# MAIN.net
KiCad netlist of a schematic drawn in Altium Designer
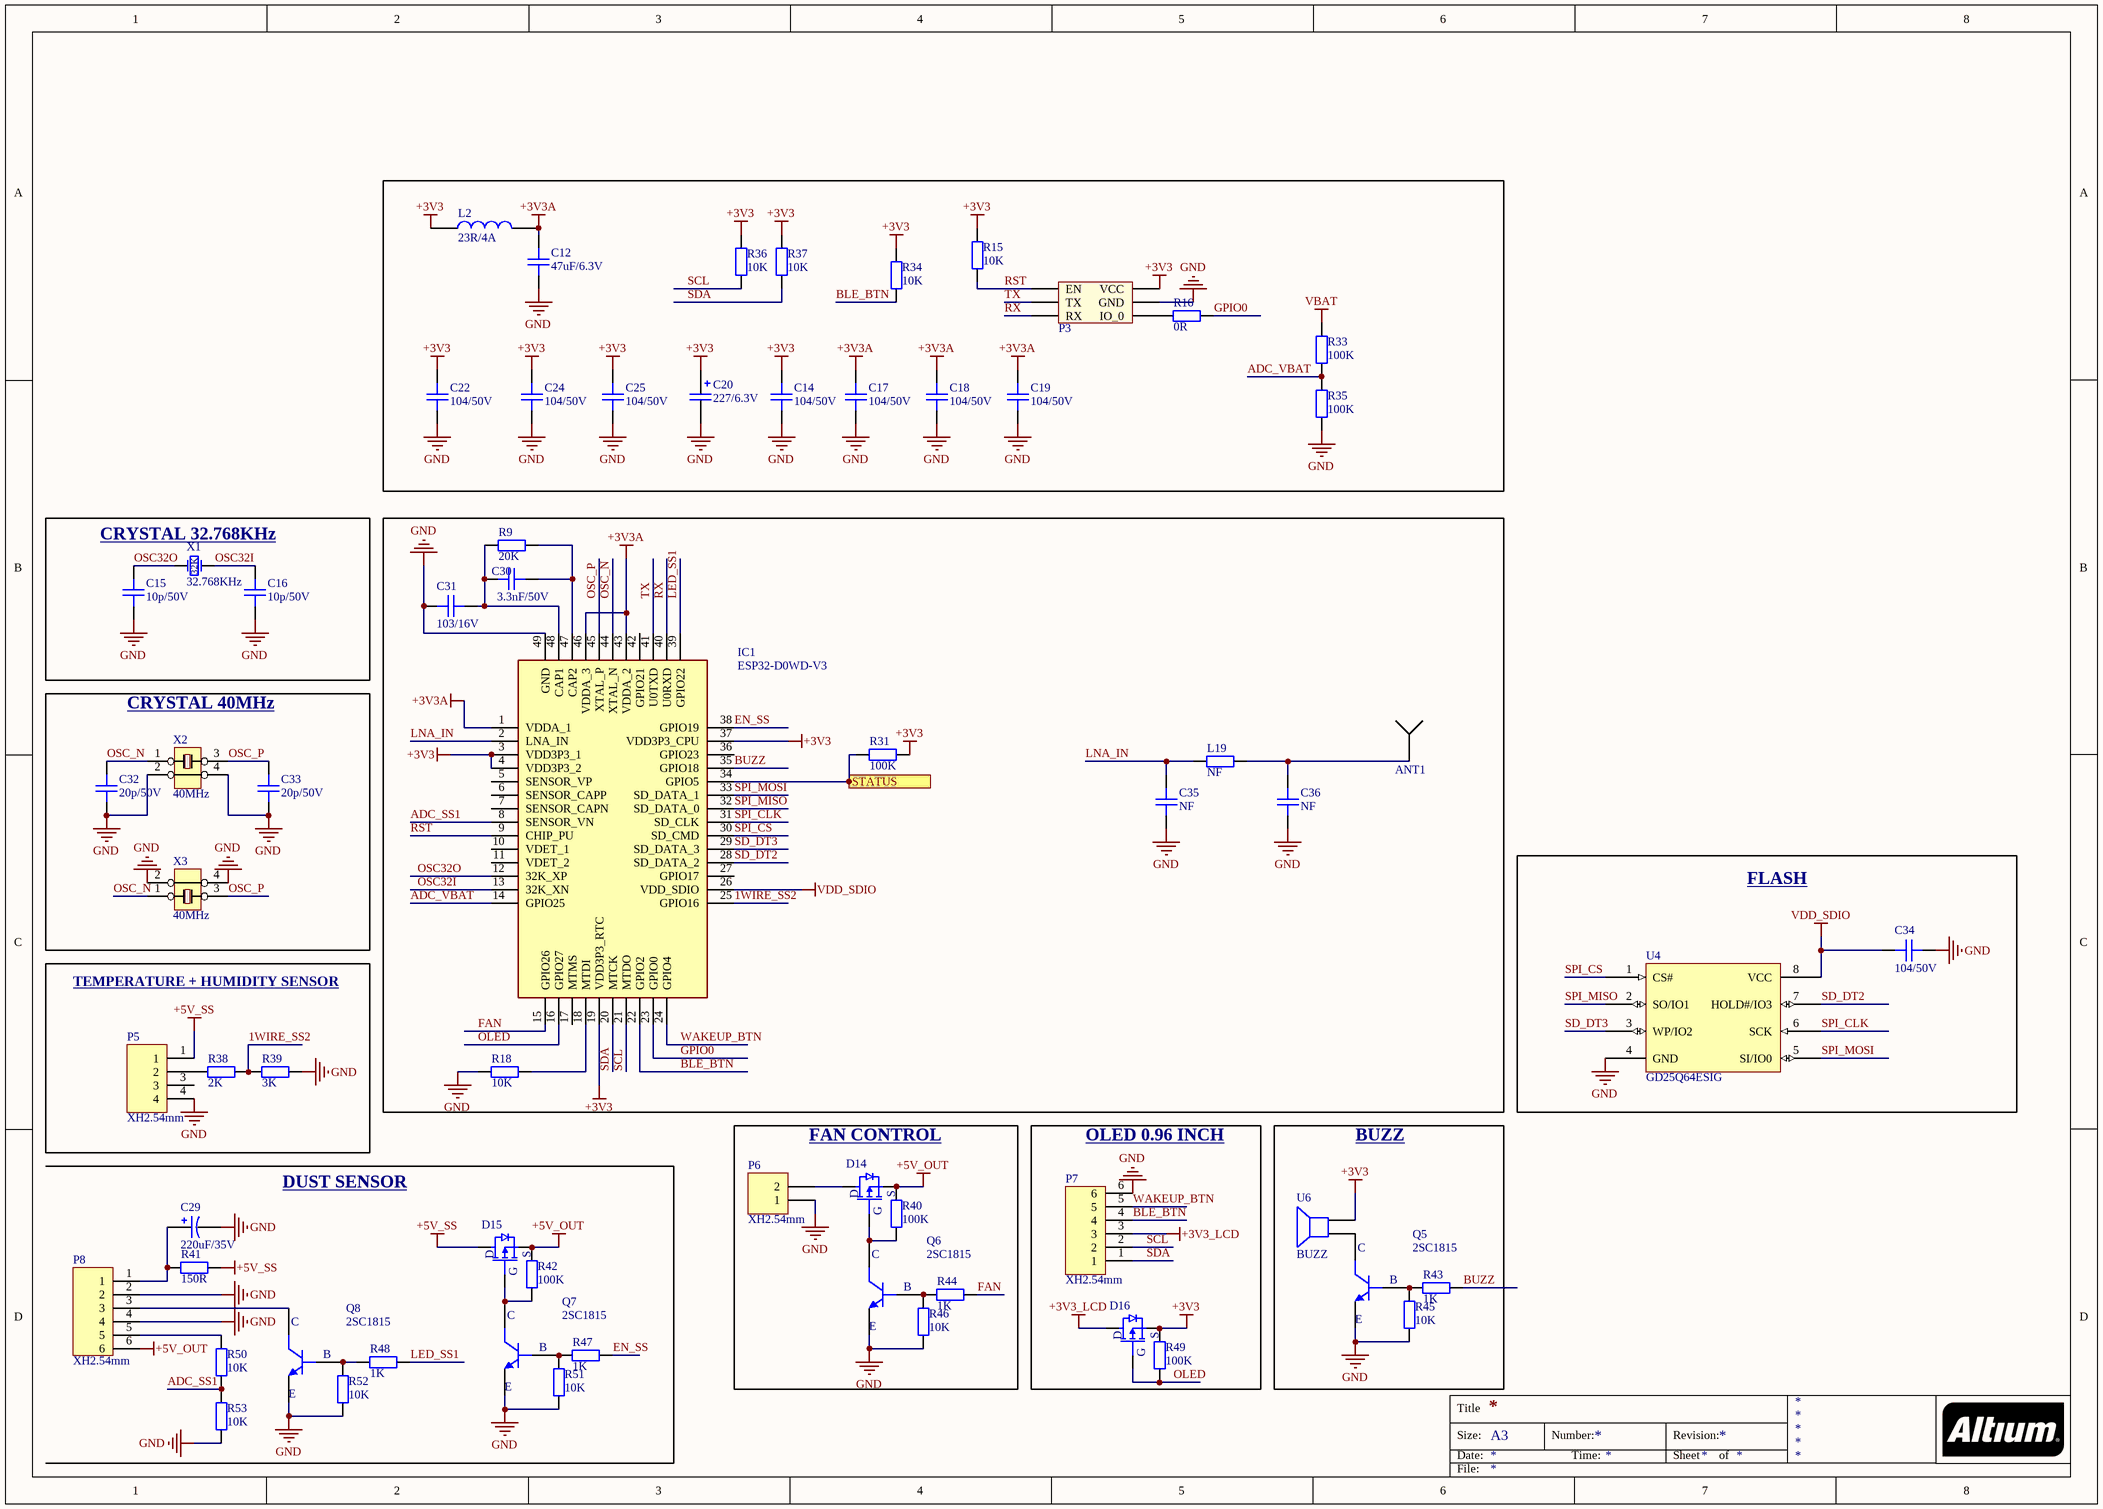
[diagram p0: MAIN.SchDoc]

(export (version "E")
  (design (tool "Eeschema 10.0.6"))
  (components
    (comp (ref "ANT1") (value "~") (footprint "SWRU120D") (libsource (lib "06.PCB Anten") (part "SWRU120D")))
    (comp (ref "C12")
      (value "47uF/6.3V")
      (footprint "CAPC-0603 (1608) - HD")
      (description "CAP CER 47UF 6.3V X5R 0603")
      (fields (field (name "MPN") "GMC10X5R476M6R3NT") (field (name "MFR") "CAL-CHIP ELECTRONICS, INC."))
      (libsource (lib "01.Passives") (part "GMC10X5R476M6R3NT"))
    )
    (comp (ref "C14")
      (value "104/50V")
      (footprint "CAPC-0603 (1608) - HD")
      (description "CAP CER 0.1uF 50V 10% X7R 0603")
      (fields (field (name "MPN") "C0603C104K5RACTU"))
      (libsource (lib "01.Passives") (part "C0603C104K5RACTU"))
    )
    (comp (ref "C15")
      (value "10p/50V")
      (footprint "CAPC-0603 (1608) - HD")
      (description "CAP CER 10pF 5% 50V NP0 0603")
      (fields (field (name "MPN") "CL10C100JB8NNND") (field (name "MFR") "Samsung Electro-Mechanics"))
      (libsource (lib "01.Passives 2") (part "CL10C100JB8NNND"))
    )
    (comp (ref "C16")
      (value "10p/50V")
      (footprint "CAPC-0603 (1608) - HD")
      (description "CAP CER 10pF 5% 50V NP0 0603")
      (fields (field (name "MPN") "CL10C100JB8NNND") (field (name "MFR") "Samsung Electro-Mechanics"))
      (libsource (lib "01.Passives 2") (part "CL10C100JB8NNND"))
    )
    (comp (ref "C17")
      (value "104/50V")
      (footprint "CAPC-0603 (1608) - HD")
      (description "CAP CER 0.1uF 50V 10% X7R 0603")
      (fields (field (name "MPN") "C0603C104K5RACTU"))
      (libsource (lib "01.Passives") (part "C0603C104K5RACTU"))
    )
    (comp (ref "C18")
      (value "104/50V")
      (footprint "CAPC-0603 (1608) - HD")
      (description "CAP CER 0.1uF 50V 10% X7R 0603")
      (fields (field (name "MPN") "C0603C104K5RACTU"))
      (libsource (lib "01.Passives") (part "C0603C104K5RACTU"))
    )
    (comp (ref "C19")
      (value "104/50V")
      (footprint "CAPC-0603 (1608) - HD")
      (description "CAP CER 0.1uF 50V 10% X7R 0603")
      (fields (field (name "MPN") "C0603C104K5RACTU"))
      (libsource (lib "01.Passives") (part "C0603C104K5RACTU"))
    )
    (comp (ref "C20")
      (value "227/6.3V")
      (footprint "CAP_TANTAL_1210(3528)")
      (description "CAP TANT POLY 220uF 20% 6.3V 3528 35mOhm ESR")
      (fields (field (name "MPN") "T520B227M006ATE035"))
      (libsource (lib "01.Passives") (part "T520B227M006ATE035"))
    )
    (comp (ref "C22")
      (value "104/50V")
      (footprint "CAPC-0603 (1608) - HD")
      (description "CAP CER 0.1uF 50V 10% X7R 0603")
      (fields (field (name "MPN") "C0603C104K5RACTU"))
      (libsource (lib "01.Passives") (part "C0603C104K5RACTU"))
    )
    (comp (ref "C24")
      (value "104/50V")
      (footprint "CAPC-0603 (1608) - HD")
      (description "CAP CER 0.1uF 50V 10% X7R 0603")
      (fields (field (name "MPN") "C0603C104K5RACTU"))
      (libsource (lib "01.Passives") (part "C0603C104K5RACTU"))
    )
    (comp (ref "C25")
      (value "104/50V")
      (footprint "CAPC-0603 (1608) - HD")
      (description "CAP CER 0.1uF 50V 10% X7R 0603")
      (fields (field (name "MPN") "C0603C104K5RACTU"))
      (libsource (lib "01.Passives") (part "C0603C104K5RACTU"))
    )
    (comp (ref "C29")
      (value "220uF/35V")
      (footprint "CAP_ALUM_D8_13mm")
      (description "CAP ALUM 220UF 20% 35V RADIAL")
      (fields (field (name "MPN") "860020574012") (field (name "MFR") "Würth Elektronik"))
      (libsource (lib "01.Passives 2") (part "860020574012"))
    )
    (comp (ref "C30")
      (value "3.3nF/50V")
      (footprint "CAPC-0603 (1608)")
      (description "CAP CER 0.033UF 50V X7R 0603")
      (fields (field (name "MPN") "C0603C333K5RACTU"))
      (libsource (lib "01.Passives") (part "C0603C333K5RACTU"))
    )
    (comp (ref "C31")
      (value "103/16V")
      (footprint "CAPC-0603 (1608)")
      (description "CAP CER 10nF 16V 10% X7R 0603")
      (fields (field (name "MPN") "CC0603KRX7R7BB103"))
      (libsource (lib "01.Passives") (part "CC0603KRX7R7BB103"))
    )
    (comp (ref "C32")
      (value "20p/50V")
      (footprint "CAPC-0603 (1608) - HD")
      (description "CAP CER 20pF 5% 50V C0G/NP0 0603")
      (fields (field (name "MPN") "CL10C200JB8NNNC"))
      (libsource (lib "01.Passives") (part "CL10C200JB8NNNC"))
    )
    (comp (ref "C33")
      (value "20p/50V")
      (footprint "CAPC-0603 (1608) - HD")
      (description "CAP CER 20pF 5% 50V C0G/NP0 0603")
      (fields (field (name "MPN") "CL10C200JB8NNNC"))
      (libsource (lib "01.Passives") (part "CL10C200JB8NNNC"))
    )
    (comp (ref "C34")
      (value "104/50V")
      (footprint "CAPC-0603 (1608) - HD")
      (description "CAP CER 0.1uF 50V 10% X7R 0603")
      (fields (field (name "MPN") "C0603C104K5RACTU"))
      (libsource (lib "01.Passives") (part "C0603C104K5RACTU"))
    )
    (comp (ref "C35")
      (value "NF")
      (footprint "CAPC-0603 (1608)")
      (description "CAP SMD, Not Fill, 0603")
      (libsource (lib "01.Passives") (part "CAPC NF 0603"))
    )
    (comp (ref "C36")
      (value "NF")
      (footprint "CAPC-0603 (1608)")
      (description "CAP SMD, Not Fill, 0603")
      (libsource (lib "01.Passives") (part "CAPC NF 0603"))
    )
    (comp (ref "D14")
      (value "20V/4A")
      (footprint "SOT23_3")
      (description "MOSFET P-CH 20V 4A SOT23")
      (fields (field (name "MFR") "Alpha & Omega Semiconductor Inc.") (field (name "MPN") "AO3415"))
      (libsource (lib "03.Semiconductor(1)") (part "AO3415"))
    )
    (comp (ref "D15")
      (value "20V/4A")
      (footprint "SOT23_3")
      (description "MOSFET P-CH 20V 4A SOT23")
      (fields (field (name "MFR") "Alpha & Omega Semiconductor Inc.") (field (name "MPN") "AO3415"))
      (libsource (lib "03.Semiconductor(1)") (part "AO3415"))
    )
    (comp (ref "D16")
      (value "20V/4A")
      (footprint "SOT23_3")
      (description "MOSFET P-CH 20V 4A SOT23")
      (fields (field (name "MFR") "Alpha & Omega Semiconductor Inc.") (field (name "MPN") "AO3415"))
      (libsource (lib "03.Semiconductor(1)") (part "AO3415"))
    )
    (comp (ref "IC1")
      (value "ESP32-D0WD-V3")
      (footprint "BST01_A04:ESP32-D0WD")
      (description "Integrated Circuit")
      (libsource (lib "*") (part "ESP32-D0WD-V3"))
    )
    (comp (ref "L2")
      (value "23R/4A")
      (footprint "IND-0603 (1608) - HD")
      (description "IND-FERRITE BEAD 23 OHM  4A 0603 1LN")
      (fields (field (name "MPN") "FBMJ1608HM230NT"))
      (libsource (lib "01.Passives 2") (part "FBMJ1608HM230NT"))
    )
    (comp (ref "L19")
      (value "NF")
      (footprint "RESC-0603 (1608)")
      (description "RES SMD, Not Fill, 0603")
      (libsource (lib "01.Passives") (part "RESC NF 0603"))
    )
    (comp (ref "P3")
      (value "DC3/6P")
      (footprint "DC3_6P_1.27")
      (fields (field (name "MPN") "DC3 6P 1.27mm") (field (name "MFR") "China"))
      (libsource (lib "04.Header-Connecter") (part "IDE_6P"))
    )
    (comp (ref "P5")
      (value "XH2.54mm")
      (footprint "XH2.54-4P")
      (description "XH2.54mmm - 4P 180 degree")
      (fields (field (name "MPN") "XH2.54-4P"))
      (libsource (lib "04.Header-Connecter") (part "XH2.54-4P"))
    )
    (comp (ref "P6")
      (value "XH2.54mm")
      (footprint "XH2.54-2P")
      (description "XH2.54mmm - 2P 180 degree")
      (fields (field (name "MPN") "XH2.54-2P") (field (name "MFR") "China"))
      (libsource (lib "04.Header-Connecter") (part "XH2.54-2P"))
    )
    (comp (ref "P7")
      (value "XH2.54mm")
      (footprint "XH2.54-6p")
      (description "XH2.54mmm - 6P 180 degree")
      (fields (field (name "MPN") "XH2.54-6P") (field (name "MFR") "CHINA"))
      (libsource (lib "") (part "XH2.54-6p_1"))
    )
    (comp (ref "P8")
      (value "XH2.54mm")
      (footprint "XH2.54-6p")
      (description "XH2.54mmm - 6P 180 degree")
      (fields (field (name "MPN") "XH2.54-6P") (field (name "MFR") "CHINA"))
      (libsource (lib "04.Header-Connecter") (part "XH2.54-6p"))
    )
    (comp (ref "Q5")
      (value "2SC1815")
      (footprint "SOT23_3")
      (description "TRANS NPN 50V 0.15A SOT23-3")
      (libsource (lib "03.Semiconductor(1)") (part "2SC1815"))
    )
    (comp (ref "Q6")
      (value "2SC1815")
      (footprint "SOT23_3")
      (description "TRANS NPN 50V 0.15A SOT23-3")
      (libsource (lib "03.Semiconductor(1)") (part "2SC1815"))
    )
    (comp (ref "Q7")
      (value "2SC1815")
      (footprint "SOT23_3")
      (description "TRANS NPN 50V 0.15A SOT23-3")
      (libsource (lib "03.Semiconductor(1)") (part "2SC1815"))
    )
    (comp (ref "Q8")
      (value "2SC1815")
      (footprint "SOT23_3")
      (description "TRANS NPN 50V 0.15A SOT23-3")
      (libsource (lib "03.Semiconductor(1)") (part "2SC1815"))
    )
    (comp (ref "R9")
      (value "20K")
      (footprint "RESC-0603 (1608)")
      (description "RES SMD 20K OHM 1% 1/10W 0603")
      (fields (field (name "MPN") "RC0603FR-0720KL"))
      (libsource (lib "01.Passives") (part "RC0603FR-0720KL"))
    )
    (comp (ref "R15")
      (value "10K")
      (footprint "RESC-0603 (1608) - HD")
      (description "RES SMD 10K OHM 1% 1/10W 0603")
      (fields (field (name "MPN") "RC0603FR-0710KL"))
      (libsource (lib "") (part "RC0603FR-0710KL_1"))
    )
    (comp (ref "R16")
      (value "0R")
      (footprint "RESC-0603 (1608) - HD")
      (description "RES SMD 0 OHM 1% 1/10W 0603")
      (fields (field (name "MPN") "RC0603FR-070R"))
      (libsource (lib "01.Passives") (part "RC0603FR-070R"))
    )
    (comp (ref "R18")
      (value "10K")
      (footprint "RESC-0603 (1608) - HD")
      (description "RES SMD 10K OHM 1% 1/10W 0603")
      (fields (field (name "MPN") "RC0603FR-0710KL"))
      (libsource (lib "01.Passives") (part "RC0603FR-0710KL"))
    )
    (comp (ref "R31")
      (value "100K")
      (footprint "RESC-0603 (1608) - HD")
      (description "RES SMD 100K OHM 1% 1/10W 0603")
      (fields (field (name "MPN") "RC0603FR-07100KL") (field (name "MFR") "Yageo"))
      (libsource (lib "") (part "RC0603FR-07100KL_1"))
    )
    (comp (ref "R33")
      (value "100K")
      (footprint "RESC-0603 (1608) - HD")
      (description "RES SMD 100K OHM 1% 1/10W 0603")
      (fields (field (name "MPN") "RC0603FR-07100KL") (field (name "MFR") "Yageo"))
      (libsource (lib "01.Passives 2") (part "RC0603FR-07100KL"))
    )
    (comp (ref "R34")
      (value "10K")
      (footprint "RESC-0603 (1608) - HD")
      (description "RES SMD 10K OHM 1% 1/10W 0603")
      (fields (field (name "MPN") "RC0603FR-0710KL") (field (name "MFR") "Yageo"))
      (libsource (lib "01.Passives 2") (part "RC0603FR-0710KL"))
    )
    (comp (ref "R35")
      (value "100K")
      (footprint "RESC-0603 (1608) - HD")
      (description "RES SMD 100K OHM 1% 1/10W 0603")
      (fields (field (name "MPN") "RC0603FR-07100KL") (field (name "MFR") "Yageo"))
      (libsource (lib "01.Passives 2") (part "RC0603FR-07100KL"))
    )
    (comp (ref "R36")
      (value "10K")
      (footprint "RESC-0603 (1608) - HD")
      (description "RES SMD 10K OHM 1% 1/10W 0603")
      (fields (field (name "MPN") "RC0603FR-0710KL") (field (name "MFR") "Yageo"))
      (libsource (lib "01.Passives 2") (part "RC0603FR-0710KL"))
    )
    (comp (ref "R37")
      (value "10K")
      (footprint "RESC-0603 (1608) - HD")
      (description "RES SMD 10K OHM 1% 1/10W 0603")
      (fields (field (name "MPN") "RC0603FR-0710KL") (field (name "MFR") "Yageo"))
      (libsource (lib "01.Passives 2") (part "RC0603FR-0710KL"))
    )
    (comp (ref "R38")
      (value "2K")
      (footprint "RESC-0603 (1608) - HD")
      (description "RES SMD 10K OHM 1% 1/10W 0603")
      (fields (field (name "MPN") "RC0603FR-0710KL") (field (name "MFR") "Yageo"))
      (libsource (lib "") (part "RC0603FR-0710KL_1"))
    )
    (comp (ref "R39")
      (value "3K")
      (footprint "RESC-0603 (1608) - HD")
      (description "RES SMD 10K OHM 1% 1/10W 0603")
      (fields (field (name "MPN") "RC0603FR-0710KL") (field (name "MFR") "Yageo"))
      (libsource (lib "") (part "RC0603FR-0710KL_1"))
    )
    (comp (ref "R40")
      (value "100K")
      (footprint "RESC-0603 (1608) - HD")
      (description "RES SMD 100K OHM 1% 1/10W 0603")
      (fields (field (name "MPN") "RC0603FR-07100KL") (field (name "MFR") "Yageo"))
      (libsource (lib "01.Passives 2") (part "RC0603FR-07100KL"))
    )
    (comp (ref "R41")
      (value "150R")
      (footprint "RESC-0603 (1608) - HD")
      (description "RES SMD 150 OHM 1% 1/10W 0603")
      (fields (field (name "MPN") "RC0603FR-07150RP") (field (name "MFR") "YAGEO"))
      (libsource (lib "01.Passives 2") (part "RC0603FR-07150RP"))
    )
    (comp (ref "R42")
      (value "100K")
      (footprint "RESC-0603 (1608) - HD")
      (description "RES SMD 100K OHM 1% 1/10W 0603")
      (fields (field (name "MPN") "RC0603FR-07100KL") (field (name "MFR") "Yageo"))
      (libsource (lib "01.Passives 2") (part "RC0603FR-07100KL"))
    )
    (comp (ref "R43")
      (value "1K")
      (footprint "RESC-0603 (1608) - HD")
      (description "RES SMD 1 KOHM 1% 1/10W 0603")
      (fields (field (name "MPN") "RC0603FR-071KL"))
      (libsource (lib "01.Passives 2") (part "RC0603FR-071KL"))
    )
    (comp (ref "R44")
      (value "1K")
      (footprint "RESC-0603 (1608) - HD")
      (description "RES SMD 1 KOHM 1% 1/10W 0603")
      (fields (field (name "MPN") "RC0603FR-071KL"))
      (libsource (lib "01.Passives 2") (part "RC0603FR-071KL"))
    )
    (comp (ref "R45")
      (value "10K")
      (footprint "RESC-0603 (1608) - HD")
      (description "RES SMD 10K OHM 1% 1/10W 0603")
      (fields (field (name "MPN") "RC0603FR-0710KL") (field (name "MFR") "Yageo"))
      (libsource (lib "01.Passives 2") (part "RC0603FR-0710KL"))
    )
    (comp (ref "R46")
      (value "10K")
      (footprint "RESC-0603 (1608) - HD")
      (description "RES SMD 10K OHM 1% 1/10W 0603")
      (fields (field (name "MPN") "RC0603FR-0710KL") (field (name "MFR") "Yageo"))
      (libsource (lib "01.Passives 2") (part "RC0603FR-0710KL"))
    )
    (comp (ref "R47")
      (value "1K")
      (footprint "RESC-0603 (1608) - HD")
      (description "RES SMD 1 KOHM 1% 1/10W 0603")
      (fields (field (name "MPN") "RC0603FR-071KL"))
      (libsource (lib "01.Passives 2") (part "RC0603FR-071KL"))
    )
    (comp (ref "R48")
      (value "1K")
      (footprint "RESC-0603 (1608) - HD")
      (description "RES SMD 1 KOHM 1% 1/10W 0603")
      (fields (field (name "MPN") "RC0603FR-071KL"))
      (libsource (lib "01.Passives 2") (part "RC0603FR-071KL"))
    )
    (comp (ref "R49")
      (value "100K")
      (footprint "RESC-0603 (1608) - HD")
      (description "RES SMD 100K OHM 1% 1/10W 0603")
      (fields (field (name "MPN") "RC0603FR-07100KL") (field (name "MFR") "Yageo"))
      (libsource (lib "01.Passives 2") (part "RC0603FR-07100KL"))
    )
    (comp (ref "R50")
      (value "10K")
      (footprint "RESC-0603 (1608) - HD")
      (description "RES SMD 10K OHM 1% 1/10W 0603")
      (fields (field (name "MPN") "RC0603FR-0710KL") (field (name "MFR") "Yageo"))
      (libsource (lib "01.Passives 2") (part "RC0603FR-0710KL"))
    )
    (comp (ref "R51")
      (value "10K")
      (footprint "RESC-0603 (1608) - HD")
      (description "RES SMD 10K OHM 1% 1/10W 0603")
      (fields (field (name "MPN") "RC0603FR-0710KL") (field (name "MFR") "Yageo"))
      (libsource (lib "01.Passives 2") (part "RC0603FR-0710KL"))
    )
    (comp (ref "R52")
      (value "10K")
      (footprint "RESC-0603 (1608) - HD")
      (description "RES SMD 10K OHM 1% 1/10W 0603")
      (fields (field (name "MPN") "RC0603FR-0710KL") (field (name "MFR") "Yageo"))
      (libsource (lib "01.Passives 2") (part "RC0603FR-0710KL"))
    )
    (comp (ref "R53")
      (value "10K")
      (footprint "RESC-0603 (1608) - HD")
      (description "RES SMD 10K OHM 1% 1/10W 0603")
      (fields (field (name "MPN") "RC0603FR-0710KL") (field (name "MFR") "Yageo"))
      (libsource (lib "01.Passives 2") (part "RC0603FR-0710KL"))
    )
    (comp (ref "U4")
      (value "GD25Q64ESIG")
      (footprint "GD25QXXE")
      (description "IC FLASH 64MBIT 133MHZ SOIC-8")
      (fields (field (name "MFR") "GD"))
      (libsource (lib "05.IC") (part "GD25Q64ESIG"))
    )
    (comp (ref "U6")
      (value "BUZZ")
      (footprint "BUZZER_through_hole")
      (description "Loudspeaker")
      (fields
        (field (name "BAPARTNUMBER") "VT-0")
        (field (name "MPN") "CLA2021")
        (field (name "PUBLISHER") "Altium Limited")
      )
      (libsource (lib "08.Miscellaneous") (part "Speaker"))
    )
    (comp (ref "X1")
      (value "32.768KHz")
      (footprint "CRYSTAL_ABS06 2x1.2mm")
      (description "CRYSTAL 32.7680KHZ 4pF SMD")
      (fields (field (name "MPN") "ABS06-107-32.768kHz-T") (field (name "MFR") "Abracon LLC"))
      (libsource (lib "01.Passives 2") (part "ABS06-107-32.768kHz-T"))
    )
    (comp (ref "X2")
      (value "40MHz")
      (footprint "OSC-40M-3225")
      (description "40MHz ±10ppm 15pF 30Ω SMD-3225 SMD Crystal Resonators RoHS")
      (fields (field (name "MPN") "TXM40M0004322HBCEO00T") (field (name "MFR") "TAE(Zhejiang Abel Elec)"))
      (libsource (lib "01.Passives") (part "TXM40M0004322HBCEO00T"))
    )
    (comp (ref "X3")
      (value "40MHz")
      (footprint "CRYSTAL-XRCGB27M120F3M10R0 (2x1.6)")
      (description "CRYSTAL 40.0000MHZ 8PF SMD")
      (fields (field (name "MPN") "XRCGB40M000F4M01R0") (field (name "MFR") "Murata Electronics"))
      (libsource (lib "01.Passives 2") (part "XRCGB40M000F4M01R0"))
    )
  )
  (nets
    (net (code "1") (name "+3V3") (class "Default")
      (node (ref "C14") (pin "2") (pinfunction "2_2") (pintype "passive"))
      (node (ref "C20") (pin "1") (pinfunction "1_1") (pintype "passive"))
      (node (ref "C22") (pin "2") (pinfunction "2_2") (pintype "passive"))
      (node (ref "C24") (pin "2") (pinfunction "2_2") (pintype "passive"))
      (node (ref "C25") (pin "2") (pinfunction "2_2") (pintype "passive"))
      (node (ref "D16") (pin "2") (pinfunction "S_2") (pintype "passive"))
      (node (ref "IC1") (pin "19") (pinfunction "VDD3P3_RTC_19") (pintype "passive"))
      (node (ref "IC1") (pin "3") (pinfunction "VDD3P3_1_3") (pintype "passive"))
      (node (ref "IC1") (pin "37") (pinfunction "VDD3P3_CPU_37") (pintype "passive"))
      (node (ref "IC1") (pin "4") (pinfunction "VDD3P3_2_4") (pintype "passive"))
      (node (ref "L2") (pin "1") (pinfunction "1_1") (pintype "passive"))
      (node (ref "P3") (pin "2") (pinfunction "VCC_2") (pintype "passive"))
      (node (ref "R15") (pin "2") (pinfunction "2_2") (pintype "passive"))
      (node (ref "R31") (pin "1") (pinfunction "1_1") (pintype "passive"))
      (node (ref "R34") (pin "2") (pinfunction "2_2") (pintype "passive"))
      (node (ref "R36") (pin "2") (pinfunction "2_2") (pintype "passive"))
      (node (ref "R37") (pin "2") (pinfunction "2_2") (pintype "passive"))
      (node (ref "R49") (pin "2") (pinfunction "2_2") (pintype "passive"))
      (node (ref "U6") (pin "1") (pinfunction "1_1") (pintype "passive"))
    )
    (net (code "2") (name "+3V3A") (class "Default")
      (node (ref "C12") (pin "2") (pinfunction "2_2") (pintype "passive"))
      (node (ref "C17") (pin "2") (pinfunction "2_2") (pintype "passive"))
      (node (ref "C18") (pin "2") (pinfunction "2_2") (pintype "passive"))
      (node (ref "C19") (pin "2") (pinfunction "2_2") (pintype "passive"))
      (node (ref "IC1") (pin "1") (pinfunction "VDDA_1_1") (pintype "passive"))
      (node (ref "IC1") (pin "43") (pinfunction "VDDA_2_43") (pintype "passive"))
      (node (ref "IC1") (pin "46") (pinfunction "VDDA_3_46") (pintype "passive"))
      (node (ref "L2") (pin "2") (pinfunction "2_2") (pintype "passive"))
    )
    (net (code "3") (name "+3V3_LCD") (class "Default")
      (node (ref "D16") (pin "3") (pinfunction "D_3") (pintype "passive"))
      (node (ref "P7") (pin "3") (pinfunction "3_3") (pintype "power_in"))
    )
    (net (code "4") (name "+5V_OUT") (class "Default")
      (node (ref "D14") (pin "2") (pinfunction "S_2") (pintype "passive"))
      (node (ref "D15") (pin "2") (pinfunction "S_2") (pintype "passive"))
      (node (ref "P8") (pin "6") (pinfunction "6_6") (pintype "passive"))
      (node (ref "R40") (pin "2") (pinfunction "2_2") (pintype "passive"))
      (node (ref "R42") (pin "2") (pinfunction "2_2") (pintype "passive"))
    )
    (net (code "5") (name "+5V_SS") (class "Default")
      (node (ref "D15") (pin "3") (pinfunction "D_3") (pintype "passive"))
      (node (ref "P5") (pin "1") (pinfunction "1_1") (pintype "passive"))
      (node (ref "R41") (pin "2") (pinfunction "2_2") (pintype "passive"))
    )
    (net (code "6") (name "/1WIRE_SS2") (class "Default")
      (node (ref "IC1") (pin "25") (pinfunction "GPIO16_25") (pintype "passive"))
      (node (ref "R38") (pin "1") (pinfunction "1_1") (pintype "passive"))
      (node (ref "R39") (pin "2") (pinfunction "2_2") (pintype "passive"))
    )
    (net (code "7") (name "/ADC_SS1") (class "Default")
      (node (ref "IC1") (pin "8") (pinfunction "SENSOR_VN_8") (pintype "passive"))
      (node (ref "R50") (pin "1") (pinfunction "1_1") (pintype "passive"))
      (node (ref "R53") (pin "2") (pinfunction "2_2") (pintype "passive"))
    )
    (net (code "8") (name "/ADC_VBAT") (class "Default")
      (node (ref "IC1") (pin "14") (pinfunction "GPIO25_14") (pintype "passive"))
      (node (ref "R33") (pin "1") (pinfunction "1_1") (pintype "passive"))
      (node (ref "R35") (pin "2") (pinfunction "2_2") (pintype "passive"))
    )
    (net (code "9") (name "/BLE_BTN") (class "Default")
      (node (ref "IC1") (pin "22") (pinfunction "GPIO2_22") (pintype "passive"))
      (node (ref "P7") (pin "4") (pinfunction "4_4") (pintype "power_in"))
      (node (ref "R34") (pin "1") (pinfunction "1_1") (pintype "passive"))
    )
    (net (code "10") (name "/BUZZ") (class "Default")
      (node (ref "IC1") (pin "35") (pinfunction "GPIO18_35") (pintype "passive"))
      (node (ref "R43") (pin "2") (pinfunction "2_2") (pintype "passive"))
    )
    (net (code "11") (name "/EN_SS") (class "Default")
      (node (ref "IC1") (pin "38") (pinfunction "GPIO19_38") (pintype "passive"))
      (node (ref "R47") (pin "2") (pinfunction "2_2") (pintype "passive"))
    )
    (net (code "12") (name "/FAN") (class "Default")
      (node (ref "IC1") (pin "15") (pinfunction "GPIO26_15") (pintype "passive"))
      (node (ref "R44") (pin "2") (pinfunction "2_2") (pintype "passive"))
    )
    (net (code "13") (name "/GPIO0") (class "Default")
      (node (ref "IC1") (pin "23") (pinfunction "GPIO0_23") (pintype "passive"))
      (node (ref "R16") (pin "2") (pinfunction "2_2") (pintype "passive"))
    )
    (net (code "14") (name "/LED_SS1") (class "Default")
      (node (ref "IC1") (pin "39") (pinfunction "GPIO22_39") (pintype "passive"))
      (node (ref "R48") (pin "2") (pinfunction "2_2") (pintype "passive"))
    )
    (net (code "15") (name "/LNA_IN") (class "Default")
      (node (ref "C35") (pin "2") (pinfunction "2_2") (pintype "passive"))
      (node (ref "IC1") (pin "2") (pinfunction "LNA_IN_2") (pintype "passive"))
      (node (ref "L19") (pin "1") (pinfunction "1_1") (pintype "passive"))
    )
    (net (code "16") (name "/OLED") (class "Default")
      (node (ref "D16") (pin "1") (pinfunction "G_1") (pintype "passive"))
      (node (ref "IC1") (pin "16") (pinfunction "GPIO27_16") (pintype "passive"))
      (node (ref "R49") (pin "1") (pinfunction "1_1") (pintype "passive"))
    )
    (net (code "17") (name "/OSC32I") (class "Default")
      (node (ref "C16") (pin "2") (pinfunction "2_2") (pintype "passive"))
      (node (ref "IC1") (pin "13") (pinfunction "32K_XN_13") (pintype "passive"))
      (node (ref "X1") (pin "2") (pinfunction "OSC2_2") (pintype "passive"))
    )
    (net (code "18") (name "/OSC32O") (class "Default")
      (node (ref "C15") (pin "2") (pinfunction "2_2") (pintype "passive"))
      (node (ref "IC1") (pin "12") (pinfunction "32K_XP_12") (pintype "passive"))
      (node (ref "X1") (pin "1") (pinfunction "OSC1_1") (pintype "passive"))
    )
    (net (code "19") (name "/OSC_N") (class "Default")
      (node (ref "C32") (pin "2") (pinfunction "2_2") (pintype "passive"))
      (node (ref "IC1") (pin "44") (pinfunction "XTAL_N_44") (pintype "passive"))
      (node (ref "X2") (pin "1") (pinfunction "1_1") (pintype "passive"))
      (node (ref "X3") (pin "1") (pinfunction "1_1") (pintype "passive"))
    )
    (net (code "20") (name "/OSC_P") (class "Default")
      (node (ref "C33") (pin "2") (pinfunction "2_2") (pintype "passive"))
      (node (ref "IC1") (pin "45") (pinfunction "XTAL_P_45") (pintype "passive"))
      (node (ref "X2") (pin "3") (pinfunction "3_3") (pintype "passive"))
      (node (ref "X3") (pin "3") (pinfunction "3_3") (pintype "passive"))
    )
    (net (code "21") (name "/RST") (class "Default")
      (node (ref "IC1") (pin "9") (pinfunction "CHIP_PU_9") (pintype "passive"))
      (node (ref "P3") (pin "1") (pinfunction "EN_1") (pintype "passive"))
      (node (ref "R15") (pin "1") (pinfunction "1_1") (pintype "passive"))
    )
    (net (code "22") (name "/RX") (class "Default")
      (node (ref "IC1") (pin "40") (pinfunction "U0RXD_40") (pintype "passive"))
      (node (ref "P3") (pin "5") (pinfunction "RX_5") (pintype "passive"))
    )
    (net (code "23") (name "/SCL") (class "Default")
      (node (ref "IC1") (pin "21") (pinfunction "MTDO_21") (pintype "passive"))
      (node (ref "P7") (pin "2") (pinfunction "2_2") (pintype "passive"))
      (node (ref "R36") (pin "1") (pinfunction "1_1") (pintype "passive"))
    )
    (net (code "24") (name "/SDA") (class "Default")
      (node (ref "IC1") (pin "20") (pinfunction "MTCK_20") (pintype "passive"))
      (node (ref "P7") (pin "1") (pinfunction "1_1") (pintype "passive"))
      (node (ref "R37") (pin "1") (pinfunction "1_1") (pintype "passive"))
    )
    (net (code "25") (name "/SD_DT2") (class "Default")
      (node (ref "IC1") (pin "28") (pinfunction "SD_DATA_2_28") (pintype "passive"))
      (node (ref "U4") (pin "7") (pinfunction "HOLD#/IO3_7") (pintype "bidirectional"))
    )
    (net (code "26") (name "/SD_DT3") (class "Default")
      (node (ref "IC1") (pin "29") (pinfunction "SD_DATA_3_29") (pintype "passive"))
      (node (ref "U4") (pin "3") (pinfunction "WP/IO2_3") (pintype "bidirectional"))
    )
    (net (code "27") (name "/SPI_CLK") (class "Default")
      (node (ref "IC1") (pin "31") (pinfunction "SD_CLK_31") (pintype "passive"))
      (node (ref "U4") (pin "6") (pinfunction "SCK_6") (pintype "input"))
    )
    (net (code "28") (name "/SPI_CS") (class "Default")
      (node (ref "IC1") (pin "30") (pinfunction "SD_CMD_30") (pintype "passive"))
      (node (ref "U4") (pin "1") (pinfunction "CS#_1") (pintype "input"))
    )
    (net (code "29") (name "/SPI_MISO") (class "Default")
      (node (ref "IC1") (pin "32") (pinfunction "SD_DATA_0_32") (pintype "passive"))
      (node (ref "U4") (pin "2") (pinfunction "SO/IO1_2") (pintype "bidirectional"))
    )
    (net (code "30") (name "/SPI_MOSI") (class "Default")
      (node (ref "IC1") (pin "33") (pinfunction "SD_DATA_1_33") (pintype "passive"))
      (node (ref "U4") (pin "5") (pinfunction "SI/IO0_5") (pintype "bidirectional"))
    )
    (net (code "31") (name "/STATUS") (class "Default")
      (node (ref "IC1") (pin "34") (pinfunction "GPIO5_34") (pintype "passive"))
      (node (ref "R31") (pin "2") (pinfunction "2_2") (pintype "passive"))
    )
    (net (code "32") (name "/TX") (class "Default")
      (node (ref "IC1") (pin "41") (pinfunction "U0TXD_41") (pintype "passive"))
      (node (ref "P3") (pin "3") (pinfunction "TX_3") (pintype "passive"))
    )
    (net (code "33") (name "/WAKEUP_BTN") (class "Default")
      (node (ref "IC1") (pin "24") (pinfunction "GPIO4_24") (pintype "passive"))
      (node (ref "P7") (pin "5") (pinfunction "5_5") (pintype "power_in"))
    )
    (net (code "34") (name "GND") (class "Default")
      (node (ref "C12") (pin "1") (pinfunction "1_1") (pintype "passive"))
      (node (ref "C14") (pin "1") (pinfunction "1_1") (pintype "passive"))
      (node (ref "C15") (pin "1") (pinfunction "1_1") (pintype "passive"))
      (node (ref "C16") (pin "1") (pinfunction "1_1") (pintype "passive"))
      (node (ref "C17") (pin "1") (pinfunction "1_1") (pintype "passive"))
      (node (ref "C18") (pin "1") (pinfunction "1_1") (pintype "passive"))
      (node (ref "C19") (pin "1") (pinfunction "1_1") (pintype "passive"))
      (node (ref "C20") (pin "2") (pinfunction "2_2") (pintype "passive"))
      (node (ref "C22") (pin "1") (pinfunction "1_1") (pintype "passive"))
      (node (ref "C24") (pin "1") (pinfunction "1_1") (pintype "passive"))
      (node (ref "C25") (pin "1") (pinfunction "1_1") (pintype "passive"))
      (node (ref "C29") (pin "2") (pinfunction "2_2") (pintype "passive"))
      (node (ref "C31") (pin "2") (pinfunction "2_2") (pintype "passive"))
      (node (ref "C32") (pin "1") (pinfunction "1_1") (pintype "passive"))
      (node (ref "C33") (pin "1") (pinfunction "1_1") (pintype "passive"))
      (node (ref "C34") (pin "1") (pinfunction "1_1") (pintype "passive"))
      (node (ref "C35") (pin "1") (pinfunction "1_1") (pintype "passive"))
      (node (ref "C36") (pin "1") (pinfunction "1_1") (pintype "passive"))
      (node (ref "IC1") (pin "49") (pinfunction "GND_49") (pintype "passive"))
      (node (ref "P3") (pin "4") (pinfunction "GND_4") (pintype "passive"))
      (node (ref "P5") (pin "4") (pinfunction "4_4") (pintype "power_in"))
      (node (ref "P6") (pin "1") (pinfunction "1_1") (pintype "passive"))
      (node (ref "P7") (pin "6") (pinfunction "6_6") (pintype "passive"))
      (node (ref "P8") (pin "2") (pinfunction "2_2") (pintype "passive"))
      (node (ref "P8") (pin "4") (pinfunction "4_4") (pintype "power_in"))
      (node (ref "Q5") (pin "2") (pinfunction "E_2") (pintype "passive"))
      (node (ref "Q6") (pin "2") (pinfunction "E_2") (pintype "passive"))
      (node (ref "Q7") (pin "2") (pinfunction "E_2") (pintype "passive"))
      (node (ref "Q8") (pin "2") (pinfunction "E_2") (pintype "passive"))
      (node (ref "R18") (pin "1") (pinfunction "1_1") (pintype "passive"))
      (node (ref "R35") (pin "1") (pinfunction "1_1") (pintype "passive"))
      (node (ref "R39") (pin "1") (pinfunction "1_1") (pintype "passive"))
      (node (ref "R45") (pin "1") (pinfunction "1_1") (pintype "passive"))
      (node (ref "R46") (pin "1") (pinfunction "1_1") (pintype "passive"))
      (node (ref "R51") (pin "1") (pinfunction "1_1") (pintype "passive"))
      (node (ref "R52") (pin "1") (pinfunction "1_1") (pintype "passive"))
      (node (ref "R53") (pin "1") (pinfunction "1_1") (pintype "passive"))
      (node (ref "U4") (pin "4") (pinfunction "GND_4") (pintype "power_in"))
      (node (ref "X2") (pin "2") (pinfunction "2_2") (pintype "passive"))
      (node (ref "X2") (pin "4") (pinfunction "4_4") (pintype "passive"))
      (node (ref "X3") (pin "2") (pinfunction "2_2") (pintype "passive"))
      (node (ref "X3") (pin "4") (pinfunction "4_4") (pintype "passive"))
    )
    (net (code "35") (name "Net-(ANT1-Pad1)") (class "Default")
      (node (ref "ANT1") (pin "1") (pinfunction "1_1") (pintype "passive"))
      (node (ref "C36") (pin "2") (pinfunction "2_2") (pintype "passive"))
      (node (ref "L19") (pin "2") (pinfunction "2_2") (pintype "passive"))
    )
    (net (code "36") (name "Net-(C29-Pad1)") (class "Default")
      (node (ref "C29") (pin "1") (pinfunction "1_1") (pintype "passive"))
      (node (ref "P8") (pin "1") (pinfunction "1_1") (pintype "passive"))
      (node (ref "R41") (pin "1") (pinfunction "1_1") (pintype "passive"))
    )
    (net (code "37") (name "Net-(D14-D)") (class "Default")
      (node (ref "D14") (pin "3") (pinfunction "D_3") (pintype "passive"))
      (node (ref "P6") (pin "2") (pinfunction "2_2") (pintype "passive"))
    )
    (net (code "38") (name "Net-(D14-G)") (class "Default")
      (node (ref "D14") (pin "1") (pinfunction "G_1") (pintype "passive"))
      (node (ref "Q6") (pin "3") (pinfunction "C_3") (pintype "passive"))
      (node (ref "R40") (pin "1") (pinfunction "1_1") (pintype "passive"))
    )
    (net (code "39") (name "Net-(D15-G)") (class "Default")
      (node (ref "D15") (pin "1") (pinfunction "G_1") (pintype "passive"))
      (node (ref "Q7") (pin "3") (pinfunction "C_3") (pintype "passive"))
      (node (ref "R42") (pin "1") (pinfunction "1_1") (pintype "passive"))
    )
    (net (code "40") (name "Net-(IC1-CAP1)") (class "Default")
      (node (ref "C30") (pin "1") (pinfunction "1_1") (pintype "passive"))
      (node (ref "C31") (pin "1") (pinfunction "1_1") (pintype "passive"))
      (node (ref "IC1") (pin "48") (pinfunction "CAP1_48") (pintype "passive"))
      (node (ref "R9") (pin "1") (pinfunction "1_1") (pintype "passive"))
    )
    (net (code "41") (name "Net-(IC1-CAP2)") (class "Default")
      (node (ref "C30") (pin "2") (pinfunction "2_2") (pintype "passive"))
      (node (ref "IC1") (pin "47") (pinfunction "CAP2_47") (pintype "passive"))
      (node (ref "R9") (pin "2") (pinfunction "2_2") (pintype "passive"))
    )
    (net (code "42") (name "Net-(IC1-MTDI)") (class "Default")
      (node (ref "IC1") (pin "18") (pinfunction "MTDI_18") (pintype "passive"))
      (node (ref "R18") (pin "2") (pinfunction "2_2") (pintype "passive"))
    )
    (net (code "43") (name "Net-(P3-IO_0)") (class "Default")
      (node (ref "P3") (pin "6") (pinfunction "IO_0_6") (pintype "passive"))
      (node (ref "R16") (pin "1") (pinfunction "1_1") (pintype "passive"))
    )
    (net (code "44") (name "Net-(P5-Pad2)") (class "Default")
      (node (ref "P5") (pin "2") (pinfunction "2_2") (pintype "passive"))
      (node (ref "R38") (pin "2") (pinfunction "2_2") (pintype "passive"))
    )
    (net (code "45") (name "Net-(P8-Pad5)") (class "Default")
      (node (ref "P8") (pin "5") (pinfunction "5_5") (pintype "power_in"))
      (node (ref "R50") (pin "2") (pinfunction "2_2") (pintype "passive"))
    )
    (net (code "46") (name "Net-(Q5-B)") (class "Default")
      (node (ref "Q5") (pin "1") (pinfunction "B_1") (pintype "passive"))
      (node (ref "R43") (pin "1") (pinfunction "1_1") (pintype "passive"))
      (node (ref "R45") (pin "2") (pinfunction "2_2") (pintype "passive"))
    )
    (net (code "47") (name "Net-(Q5-C)") (class "Default")
      (node (ref "Q5") (pin "3") (pinfunction "C_3") (pintype "passive"))
      (node (ref "U6") (pin "2") (pinfunction "2_2") (pintype "passive"))
    )
    (net (code "48") (name "Net-(Q6-B)") (class "Default")
      (node (ref "Q6") (pin "1") (pinfunction "B_1") (pintype "passive"))
      (node (ref "R44") (pin "1") (pinfunction "1_1") (pintype "passive"))
      (node (ref "R46") (pin "2") (pinfunction "2_2") (pintype "passive"))
    )
    (net (code "49") (name "Net-(Q7-B)") (class "Default")
      (node (ref "Q7") (pin "1") (pinfunction "B_1") (pintype "passive"))
      (node (ref "R47") (pin "1") (pinfunction "1_1") (pintype "passive"))
      (node (ref "R51") (pin "2") (pinfunction "2_2") (pintype "passive"))
    )
    (net (code "50") (name "Net-(Q8-B)") (class "Default")
      (node (ref "Q8") (pin "1") (pinfunction "B_1") (pintype "passive"))
      (node (ref "R48") (pin "1") (pinfunction "1_1") (pintype "passive"))
      (node (ref "R52") (pin "2") (pinfunction "2_2") (pintype "passive"))
    )
    (net (code "51") (name "Net-(Q8-C)") (class "Default")
      (node (ref "P8") (pin "3") (pinfunction "3_3") (pintype "power_in"))
      (node (ref "Q8") (pin "3") (pinfunction "C_3") (pintype "passive"))
    )
    (net (code "52") (name "VBAT") (class "Default")
      (node (ref "R33") (pin "2") (pinfunction "2_2") (pintype "passive"))
    )
    (net (code "53") (name "VDD_SDIO") (class "Default")
      (node (ref "C34") (pin "2") (pinfunction "2_2") (pintype "passive"))
      (node (ref "IC1") (pin "26") (pinfunction "VDD_SDIO_26") (pintype "passive"))
      (node (ref "U4") (pin "8") (pinfunction "VCC_8") (pintype "power_in"))
    )
    (net (code "54") (name "unconnected-(IC1-GPIO17-Pad27)") (class "Default")
      (node (ref "IC1") (pin "27") (pinfunction "GPIO17_27") (pintype "passive"))
    )
    (net (code "55") (name "unconnected-(IC1-GPIO21-Pad42)") (class "Default")
      (node (ref "IC1") (pin "42") (pinfunction "GPIO21_42") (pintype "passive"))
    )
    (net (code "56") (name "unconnected-(IC1-GPIO23-Pad36)") (class "Default")
      (node (ref "IC1") (pin "36") (pinfunction "GPIO23_36") (pintype "passive"))
    )
    (net (code "57") (name "unconnected-(IC1-MTMS-Pad17)") (class "Default")
      (node (ref "IC1") (pin "17") (pinfunction "MTMS_17") (pintype "passive"))
    )
    (net (code "58") (name "unconnected-(IC1-SENSOR_CAPN-Pad7)") (class "Default")
      (node (ref "IC1") (pin "7") (pinfunction "SENSOR_CAPN_7") (pintype "passive"))
    )
    (net (code "59") (name "unconnected-(IC1-SENSOR_CAPP-Pad6)") (class "Default")
      (node (ref "IC1") (pin "6") (pinfunction "SENSOR_CAPP_6") (pintype "passive"))
    )
    (net (code "60") (name "unconnected-(IC1-SENSOR_VP-Pad5)") (class "Default")
      (node (ref "IC1") (pin "5") (pinfunction "SENSOR_VP_5") (pintype "passive"))
    )
    (net (code "61") (name "unconnected-(IC1-VDET_1-Pad10)") (class "Default")
      (node (ref "IC1") (pin "10") (pinfunction "VDET_1_10") (pintype "passive"))
    )
    (net (code "62") (name "unconnected-(IC1-VDET_2-Pad11)") (class "Default")
      (node (ref "IC1") (pin "11") (pinfunction "VDET_2_11") (pintype "passive"))
    )
    (net (code "63") (name "unconnected-(P5-Pad3)") (class "Default")
      (node (ref "P5") (pin "3") (pinfunction "3_3") (pintype "power_in"))
    )
  )
)
